# primus.net
KiCad netlist of a schematic drawn in EAGLE
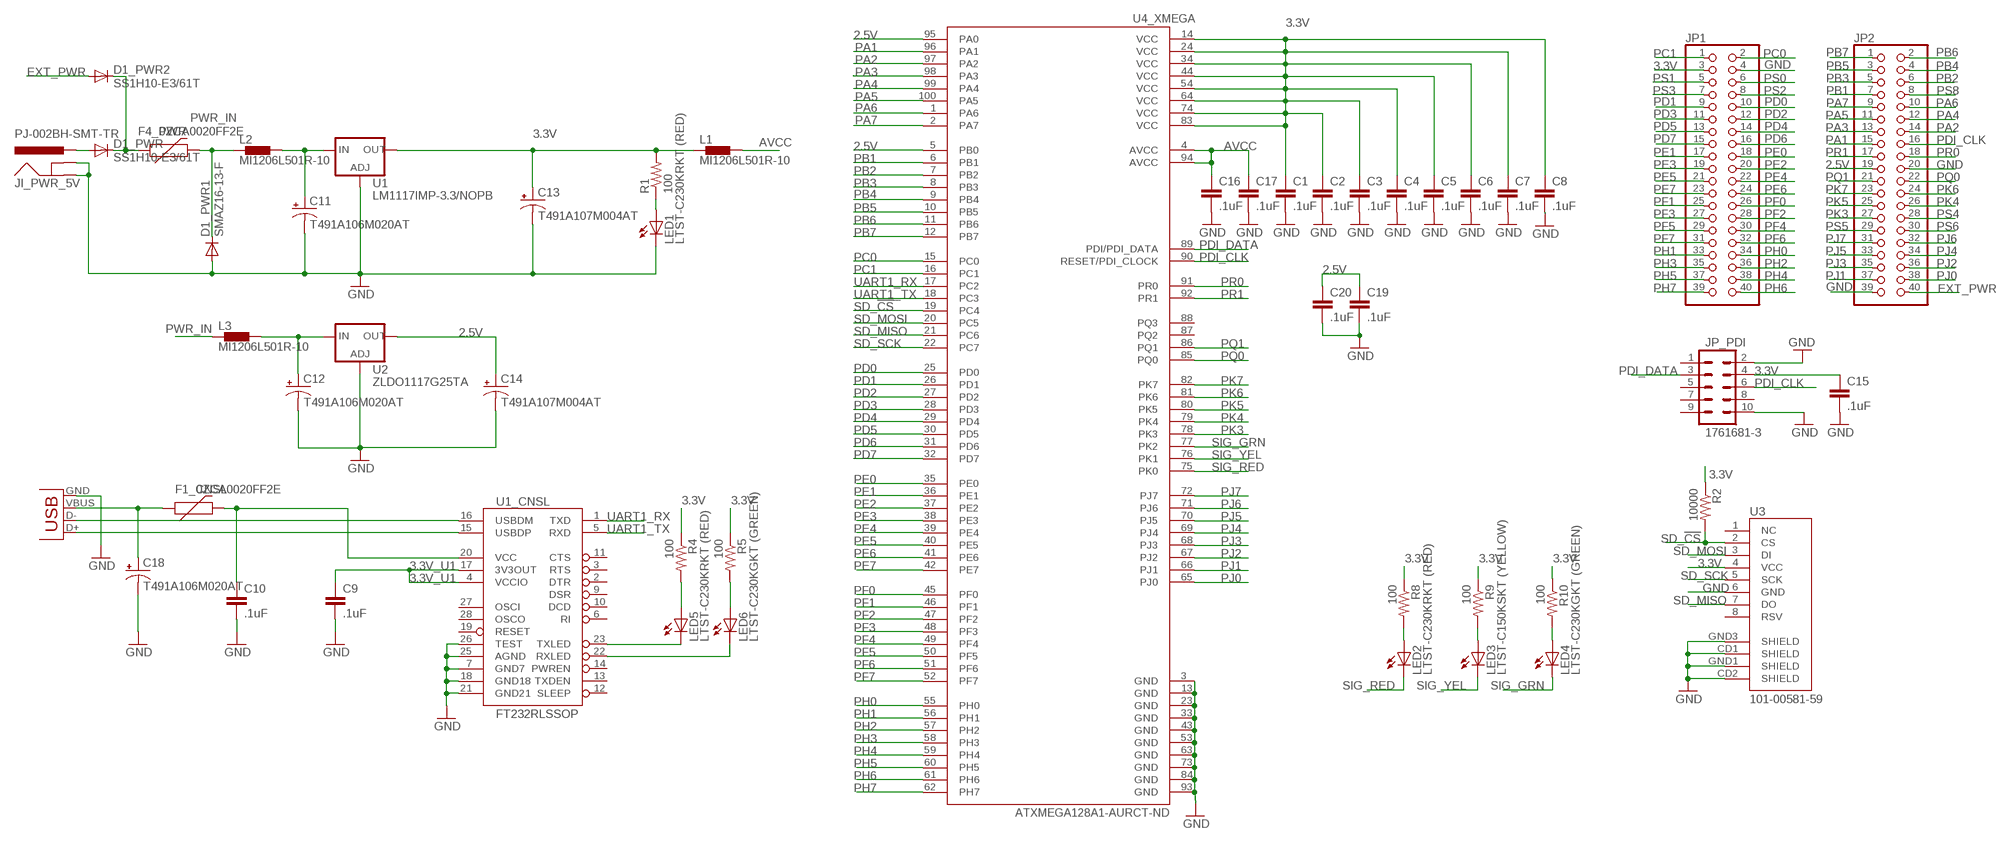
[diagram p0: schematic, sheet 1]

(export (version "E")
  (design (tool "Eeschema 10.0.6"))
  (components
    (comp (ref "C1")
      (value ".1uF")
      (footprint "eagle-import:0603-CAP")
      (libsource (lib "eagle-import") (part "CAP0603-CAP"))
    )
    (comp (ref "C2")
      (value ".1uF")
      (footprint "eagle-import:0603-CAP")
      (libsource (lib "eagle-import") (part "CAP0603-CAP"))
    )
    (comp (ref "C3")
      (value ".1uF")
      (footprint "eagle-import:0603-CAP")
      (libsource (lib "eagle-import") (part "CAP0603-CAP"))
    )
    (comp (ref "C4")
      (value ".1uF")
      (footprint "eagle-import:0603-CAP")
      (libsource (lib "eagle-import") (part "CAP0603-CAP"))
    )
    (comp (ref "C5")
      (value ".1uF")
      (footprint "eagle-import:0603-CAP")
      (libsource (lib "eagle-import") (part "CAP0603-CAP"))
    )
    (comp (ref "C6")
      (value ".1uF")
      (footprint "eagle-import:0603-CAP")
      (libsource (lib "eagle-import") (part "CAP0603-CAP"))
    )
    (comp (ref "C7")
      (value ".1uF")
      (footprint "eagle-import:0603-CAP")
      (libsource (lib "eagle-import") (part "CAP0603-CAP"))
    )
    (comp (ref "C8")
      (value ".1uF")
      (footprint "eagle-import:0603-CAP")
      (libsource (lib "eagle-import") (part "CAP0603-CAP"))
    )
    (comp (ref "C9")
      (value ".1uF")
      (footprint "eagle-import:0603-CAP")
      (libsource (lib "eagle-import") (part "CAP0603-CAP"))
    )
    (comp (ref "C10")
      (value ".1uF")
      (footprint "eagle-import:0603-CAP")
      (libsource (lib "eagle-import") (part "CAP0603-CAP"))
    )
    (comp (ref "C11")
      (value "T491A106M020AT")
      (footprint "eagle-import:EIA3216")
      (libsource (lib "eagle-import") (part "CAP_POL1206"))
    )
    (comp (ref "C12")
      (value "T491A106M020AT")
      (footprint "eagle-import:EIA3216")
      (libsource (lib "eagle-import") (part "CAP_POL1206"))
    )
    (comp (ref "C13")
      (value "T491A107M004AT")
      (footprint "eagle-import:EIA3216")
      (libsource (lib "eagle-import") (part "CAP_POL1206"))
    )
    (comp (ref "C14")
      (value "T491A107M004AT")
      (footprint "eagle-import:EIA3216")
      (libsource (lib "eagle-import") (part "CAP_POL1206"))
    )
    (comp (ref "C15")
      (value ".1uF")
      (footprint "eagle-import:0603-CAP")
      (libsource (lib "eagle-import") (part "CAP0603-CAP"))
    )
    (comp (ref "C16")
      (value ".1uF")
      (footprint "eagle-import:0603-CAP")
      (libsource (lib "eagle-import") (part "CAP0603-CAP"))
    )
    (comp (ref "C17")
      (value ".1uF")
      (footprint "eagle-import:0603-CAP")
      (libsource (lib "eagle-import") (part "CAP0603-CAP"))
    )
    (comp (ref "C18")
      (value "T491A106M020AT")
      (footprint "eagle-import:EIA3216")
      (libsource (lib "eagle-import") (part "CAP_POL1206"))
    )
    (comp (ref "C19")
      (value ".1uF")
      (footprint "eagle-import:0603-CAP")
      (libsource (lib "eagle-import") (part "CAP0603-CAP"))
    )
    (comp (ref "C20")
      (value ".1uF")
      (footprint "eagle-import:0603-CAP")
      (libsource (lib "eagle-import") (part "CAP0603-CAP"))
    )
    (comp (ref "D1_PWR")
      (value "SS1H10-E3/61T")
      (footprint "eagle-import:SMA-DIODE")
      (libsource (lib "eagle-import") (part "DIODESMA"))
    )
    (comp (ref "D1_PWR1")
      (value "SMAZ16-13-F")
      (footprint "eagle-import:SMA-DIODE")
      (libsource (lib "eagle-import") (part "DIODESMA"))
    )
    (comp (ref "D1_PWR2")
      (value "SS1H10-E3/61T")
      (footprint "eagle-import:SMA-DIODE")
      (libsource (lib "eagle-import") (part "DIODESMA"))
    )
    (comp (ref "F1_CNSL")
      (value "0ZCA0020FF2E")
      (footprint "eagle-import:PTC-1206")
      (libsource (lib "eagle-import") (part "PTCSMD"))
    )
    (comp (ref "F4_PWR")
      (value "0ZCA0020FF2E")
      (footprint "eagle-import:PTC-1206")
      (libsource (lib "eagle-import") (part "PTCSMD"))
    )
    (comp (ref "JI_PWR_5V")
      (value "PJ-002BH-SMT-TR")
      (footprint "eagle-import:POWER_JACK_SMD")
      (libsource (lib "eagle-import") (part "POWER_JACKSMD"))
    )
    (comp (ref "JP1")
      (value "PINHD-2X20")
      (footprint "eagle-import:2X20")
      (libsource (lib "eagle-import") (part "PINHD-2X20"))
    )
    (comp (ref "JP2")
      (value "PINHD-2X20")
      (footprint "eagle-import:2X20")
      (libsource (lib "eagle-import") (part "PINHD-2X20"))
    )
    (comp (ref "JP_PDI")
      (value "1761681-3")
      (footprint "eagle-import:2X5-SHROUDED")
      (libsource (lib "eagle-import") (part "M05X2SHD"))
    )
    (comp (ref "L1")
      (value "MI1206L501R-10")
      (footprint "eagle-import:1206")
      (libsource (lib "eagle-import") (part "MI1206L501R-10"))
    )
    (comp (ref "L2")
      (value "MI1206L501R-10")
      (footprint "eagle-import:1206")
      (libsource (lib "eagle-import") (part "MI1206L501R-10"))
    )
    (comp (ref "L3")
      (value "MI1206L501R-10")
      (footprint "eagle-import:1206")
      (libsource (lib "eagle-import") (part "MI1206L501R-10"))
    )
    (comp (ref "LED1")
      (value "LTST-C230KRKT (RED)")
      (footprint "eagle-import:LED-1206")
      (libsource (lib "eagle-import") (part "LED1206"))
    )
    (comp (ref "LED2")
      (value "LTST-C230KRKT (RED)")
      (footprint "eagle-import:LED-1206")
      (libsource (lib "eagle-import") (part "LED1206"))
    )
    (comp (ref "LED3")
      (value "LTST-C150KSKT (YELLOW)")
      (footprint "eagle-import:LED-1206")
      (libsource (lib "eagle-import") (part "LED1206"))
    )
    (comp (ref "LED4")
      (value "LTST-C230KGKT (GREEN)")
      (footprint "eagle-import:LED-1206")
      (libsource (lib "eagle-import") (part "LED1206"))
    )
    (comp (ref "LED5")
      (value "LTST-C230KRKT (RED)")
      (footprint "eagle-import:LED-1206")
      (libsource (lib "eagle-import") (part "LED1206"))
    )
    (comp (ref "LED6")
      (value "LTST-C230KGKT (GREEN)")
      (footprint "eagle-import:LED-1206")
      (libsource (lib "eagle-import") (part "LED1206"))
    )
    (comp (ref "R1")
      (value "100")
      (footprint "eagle-import:0603-RES")
      (libsource (lib "eagle-import") (part "RESISTOR0603-RES"))
    )
    (comp (ref "R2")
      (value "10000")
      (footprint "eagle-import:0603-RES")
      (libsource (lib "eagle-import") (part "RESISTOR0603-RES"))
    )
    (comp (ref "R4")
      (value "100")
      (footprint "eagle-import:0603-RES")
      (libsource (lib "eagle-import") (part "RESISTOR0603-RES"))
    )
    (comp (ref "R5")
      (value "100")
      (footprint "eagle-import:0603-RES")
      (libsource (lib "eagle-import") (part "RESISTOR0603-RES"))
    )
    (comp (ref "R8")
      (value "100")
      (footprint "eagle-import:0603-RES")
      (libsource (lib "eagle-import") (part "RESISTOR0603-RES"))
    )
    (comp (ref "R9")
      (value "100")
      (footprint "eagle-import:0603-RES")
      (libsource (lib "eagle-import") (part "RESISTOR0603-RES"))
    )
    (comp (ref "R10")
      (value "100")
      (footprint "eagle-import:0603-RES")
      (libsource (lib "eagle-import") (part "RESISTOR0603-RES"))
    )
    (comp (ref "U1")
      (value "LM1117IMP-3.3/NOPB")
      (footprint "eagle-import:SOT223")
      (libsource (lib "eagle-import") (part "V_REG_317SMD"))
    )
    (comp (ref "U1_CNSL")
      (value "FT232RLSSOP")
      (footprint "eagle-import:SSOP28DB")
      (libsource (lib "eagle-import") (part "FT232RLSSOP"))
    )
    (comp (ref "U2")
      (value "ZLDO1117G25TA")
      (footprint "eagle-import:SOT223")
      (libsource (lib "eagle-import") (part "V_REG_317SMD"))
    )
    (comp (ref "U3")
      (value "101-00581-59")
      (footprint "eagle-import:MICRO-SD-SOCKET-PP")
      (libsource (lib "eagle-import") (part "USD-SOCKETNEW"))
    )
    (comp (ref "U4_XMEGA")
      (value "ATXMEGA128A1-AURCT-ND")
      (footprint "eagle-import:TQFP-100-14X14MM")
      (libsource (lib "eagle-import") (part "XMEGA-100SMD"))
    )
    (comp (ref "X2_CNSL")
      (value "UX60A-MB-5ST")
      (footprint "eagle-import:USB-MINIB")
      (libsource (lib "eagle-import") (part "USBSMD"))
    )
  )
  (nets
    (net (code "1") (name "/2.5V") (class "Default")
      (node (ref "C14") (pin "A") (pinfunction "+_A") (pintype "passive"))
      (node (ref "C19") (pin "1") (pinfunction "1_1") (pintype "passive"))
      (node (ref "C20") (pin "1") (pinfunction "1_1") (pintype "passive"))
      (node (ref "JP2") (pin "19") (pinfunction "19_19") (pintype "passive"))
      (node (ref "U2") (pin "2") (pinfunction "OUT_2") (pintype "output"))
      (node (ref "U4_XMEGA") (pin "5") (pinfunction "PB0_5") (pintype "bidirectional"))
      (node (ref "U4_XMEGA") (pin "95") (pinfunction "PA0_95") (pintype "bidirectional"))
    )
    (net (code "2") (name "/3.3V") (class "Default")
      (node (ref "C1") (pin "1") (pinfunction "1_1") (pintype "passive"))
      (node (ref "C13") (pin "A") (pinfunction "+_A") (pintype "passive"))
      (node (ref "C15") (pin "1") (pinfunction "1_1") (pintype "passive"))
      (node (ref "C2") (pin "1") (pinfunction "1_1") (pintype "passive"))
      (node (ref "C3") (pin "1") (pinfunction "1_1") (pintype "passive"))
      (node (ref "C4") (pin "1") (pinfunction "1_1") (pintype "passive"))
      (node (ref "C5") (pin "1") (pinfunction "1_1") (pintype "passive"))
      (node (ref "C6") (pin "1") (pinfunction "1_1") (pintype "passive"))
      (node (ref "C7") (pin "1") (pinfunction "1_1") (pintype "passive"))
      (node (ref "C8") (pin "1") (pinfunction "1_1") (pintype "passive"))
      (node (ref "JP1") (pin "3") (pinfunction "3_3") (pintype "passive"))
      (node (ref "JP_PDI") (pin "4") (pinfunction "4_4") (pintype "passive"))
      (node (ref "L1") (pin "1") (pinfunction "1_1") (pintype "passive"))
      (node (ref "R1") (pin "2") (pinfunction "2_2") (pintype "passive"))
      (node (ref "R10") (pin "1") (pinfunction "1_1") (pintype "passive"))
      (node (ref "R2") (pin "1") (pinfunction "1_1") (pintype "passive"))
      (node (ref "R4") (pin "1") (pinfunction "1_1") (pintype "passive"))
      (node (ref "R5") (pin "1") (pinfunction "1_1") (pintype "passive"))
      (node (ref "R8") (pin "1") (pinfunction "1_1") (pintype "passive"))
      (node (ref "R9") (pin "1") (pinfunction "1_1") (pintype "passive"))
      (node (ref "U1") (pin "2") (pinfunction "OUT_2") (pintype "output"))
      (node (ref "U3") (pin "4") (pinfunction "VCC_4") (pintype "bidirectional"))
      (node (ref "U4_XMEGA") (pin "14") (pinfunction "VCC_14") (pintype "bidirectional"))
      (node (ref "U4_XMEGA") (pin "24") (pinfunction "VCC_24") (pintype "bidirectional"))
      (node (ref "U4_XMEGA") (pin "34") (pinfunction "VCC_34") (pintype "bidirectional"))
      (node (ref "U4_XMEGA") (pin "44") (pinfunction "VCC_44") (pintype "bidirectional"))
      (node (ref "U4_XMEGA") (pin "54") (pinfunction "VCC_54") (pintype "bidirectional"))
      (node (ref "U4_XMEGA") (pin "64") (pinfunction "VCC_64") (pintype "bidirectional"))
      (node (ref "U4_XMEGA") (pin "74") (pinfunction "VCC_74") (pintype "bidirectional"))
      (node (ref "U4_XMEGA") (pin "83") (pinfunction "VCC_83") (pintype "bidirectional"))
    )
    (net (code "3") (name "/3.3V_U1") (class "Default")
      (node (ref "C9") (pin "1") (pinfunction "1_1") (pintype "passive"))
      (node (ref "U1_CNSL") (pin "17") (pinfunction "3V3OUT_17") (pintype "output"))
      (node (ref "U1_CNSL") (pin "4") (pinfunction "VCCIO_4") (pintype "power_in"))
    )
    (net (code "4") (name "/AVCC") (class "Default")
      (node (ref "C16") (pin "1") (pinfunction "1_1") (pintype "passive"))
      (node (ref "C17") (pin "1") (pinfunction "1_1") (pintype "passive"))
      (node (ref "L1") (pin "2") (pinfunction "2_2") (pintype "passive"))
      (node (ref "U4_XMEGA") (pin "4") (pinfunction "AVCC_4") (pintype "bidirectional"))
      (node (ref "U4_XMEGA") (pin "94") (pinfunction "AVCC_94") (pintype "bidirectional"))
    )
    (net (code "5") (name "/EXT_PWR") (class "Default")
      (node (ref "D1_PWR2") (pin "A") (pinfunction "A_A") (pintype "passive"))
      (node (ref "JP2") (pin "40") (pinfunction "40_40") (pintype "passive"))
    )
    (net (code "6") (name "/PA1") (class "Default")
      (node (ref "JP2") (pin "15") (pinfunction "15_15") (pintype "passive"))
      (node (ref "U4_XMEGA") (pin "96") (pinfunction "PA1_96") (pintype "bidirectional"))
    )
    (net (code "7") (name "/PA2") (class "Default")
      (node (ref "JP2") (pin "14") (pinfunction "14_14") (pintype "passive"))
      (node (ref "U4_XMEGA") (pin "97") (pinfunction "PA2_97") (pintype "bidirectional"))
    )
    (net (code "8") (name "/PA3") (class "Default")
      (node (ref "JP2") (pin "13") (pinfunction "13_13") (pintype "passive"))
      (node (ref "U4_XMEGA") (pin "98") (pinfunction "PA3_98") (pintype "bidirectional"))
    )
    (net (code "9") (name "/PA4") (class "Default")
      (node (ref "JP2") (pin "12") (pinfunction "12_12") (pintype "passive"))
      (node (ref "U4_XMEGA") (pin "99") (pinfunction "PA4_99") (pintype "bidirectional"))
    )
    (net (code "10") (name "/PA5") (class "Default")
      (node (ref "JP2") (pin "11") (pinfunction "11_11") (pintype "passive"))
      (node (ref "U4_XMEGA") (pin "100") (pinfunction "PA5_100") (pintype "bidirectional"))
    )
    (net (code "11") (name "/PA6") (class "Default")
      (node (ref "JP2") (pin "10") (pinfunction "10_10") (pintype "passive"))
      (node (ref "U4_XMEGA") (pin "1") (pinfunction "PA6_1") (pintype "bidirectional"))
    )
    (net (code "12") (name "/PA7") (class "Default")
      (node (ref "JP2") (pin "9") (pinfunction "9_9") (pintype "passive"))
      (node (ref "U4_XMEGA") (pin "2") (pinfunction "PA7_2") (pintype "bidirectional"))
    )
    (net (code "13") (name "/PB1") (class "Default")
      (node (ref "JP2") (pin "7") (pinfunction "7_7") (pintype "passive"))
      (node (ref "U4_XMEGA") (pin "6") (pinfunction "PB1_6") (pintype "bidirectional"))
    )
    (net (code "14") (name "/PB2") (class "Default")
      (node (ref "JP2") (pin "6") (pinfunction "6_6") (pintype "passive"))
      (node (ref "U4_XMEGA") (pin "7") (pinfunction "PB2_7") (pintype "bidirectional"))
    )
    (net (code "15") (name "/PB3") (class "Default")
      (node (ref "JP2") (pin "5") (pinfunction "5_5") (pintype "passive"))
      (node (ref "U4_XMEGA") (pin "8") (pinfunction "PB3_8") (pintype "bidirectional"))
    )
    (net (code "16") (name "/PB4") (class "Default")
      (node (ref "JP2") (pin "4") (pinfunction "4_4") (pintype "passive"))
      (node (ref "U4_XMEGA") (pin "9") (pinfunction "PB4_9") (pintype "bidirectional"))
    )
    (net (code "17") (name "/PB5") (class "Default")
      (node (ref "JP2") (pin "3") (pinfunction "3_3") (pintype "passive"))
      (node (ref "U4_XMEGA") (pin "10") (pinfunction "PB5_10") (pintype "bidirectional"))
    )
    (net (code "18") (name "/PB6") (class "Default")
      (node (ref "JP2") (pin "2") (pinfunction "2_2") (pintype "passive"))
      (node (ref "U4_XMEGA") (pin "11") (pinfunction "PB6_11") (pintype "bidirectional"))
    )
    (net (code "19") (name "/PB7") (class "Default")
      (node (ref "JP2") (pin "1") (pinfunction "1_1") (pintype "passive"))
      (node (ref "U4_XMEGA") (pin "12") (pinfunction "PB7_12") (pintype "bidirectional"))
    )
    (net (code "20") (name "/PC0") (class "Default")
      (node (ref "JP1") (pin "2") (pinfunction "2_2") (pintype "passive"))
      (node (ref "U4_XMEGA") (pin "15") (pinfunction "PC0_15") (pintype "bidirectional"))
    )
    (net (code "21") (name "/PC1") (class "Default")
      (node (ref "JP1") (pin "1") (pinfunction "1_1") (pintype "passive"))
      (node (ref "U4_XMEGA") (pin "16") (pinfunction "PC1_16") (pintype "bidirectional"))
    )
    (net (code "22") (name "/PD0") (class "Default")
      (node (ref "JP1") (pin "10") (pinfunction "10_10") (pintype "passive"))
      (node (ref "U4_XMEGA") (pin "25") (pinfunction "PD0_25") (pintype "bidirectional"))
    )
    (net (code "23") (name "/PD1") (class "Default")
      (node (ref "JP1") (pin "9") (pinfunction "9_9") (pintype "passive"))
      (node (ref "U4_XMEGA") (pin "26") (pinfunction "PD1_26") (pintype "bidirectional"))
    )
    (net (code "24") (name "/PD2") (class "Default")
      (node (ref "JP1") (pin "12") (pinfunction "12_12") (pintype "passive"))
      (node (ref "U4_XMEGA") (pin "27") (pinfunction "PD2_27") (pintype "bidirectional"))
    )
    (net (code "25") (name "/PD3") (class "Default")
      (node (ref "JP1") (pin "11") (pinfunction "11_11") (pintype "passive"))
      (node (ref "U4_XMEGA") (pin "28") (pinfunction "PD3_28") (pintype "bidirectional"))
    )
    (net (code "26") (name "/PD4") (class "Default")
      (node (ref "JP1") (pin "14") (pinfunction "14_14") (pintype "passive"))
      (node (ref "U4_XMEGA") (pin "29") (pinfunction "PD4_29") (pintype "bidirectional"))
    )
    (net (code "27") (name "/PD5") (class "Default")
      (node (ref "JP1") (pin "13") (pinfunction "13_13") (pintype "passive"))
      (node (ref "U4_XMEGA") (pin "30") (pinfunction "PD5_30") (pintype "bidirectional"))
    )
    (net (code "28") (name "/PD6") (class "Default")
      (node (ref "JP1") (pin "16") (pinfunction "16_16") (pintype "passive"))
      (node (ref "U4_XMEGA") (pin "31") (pinfunction "PD6_31") (pintype "bidirectional"))
    )
    (net (code "29") (name "/PD7") (class "Default")
      (node (ref "JP1") (pin "15") (pinfunction "15_15") (pintype "passive"))
      (node (ref "U4_XMEGA") (pin "32") (pinfunction "PD7_32") (pintype "bidirectional"))
    )
    (net (code "30") (name "/PDI_CLK") (class "Default")
      (node (ref "JP2") (pin "16") (pinfunction "16_16") (pintype "passive"))
      (node (ref "JP_PDI") (pin "6") (pinfunction "6_6") (pintype "passive"))
      (node (ref "U4_XMEGA") (pin "90") (pinfunction "RESET/PDI_CLOCK_90") (pintype "bidirectional"))
    )
    (net (code "31") (name "/PDI_DATA") (class "Default")
      (node (ref "JP_PDI") (pin "3") (pinfunction "3_3") (pintype "passive"))
      (node (ref "U4_XMEGA") (pin "89") (pinfunction "PDI/PDI_DATA_89") (pintype "bidirectional"))
    )
    (net (code "32") (name "/PE0") (class "Default")
      (node (ref "JP1") (pin "18") (pinfunction "18_18") (pintype "passive"))
      (node (ref "U4_XMEGA") (pin "35") (pinfunction "PE0_35") (pintype "bidirectional"))
    )
    (net (code "33") (name "/PE1") (class "Default")
      (node (ref "JP1") (pin "17") (pinfunction "17_17") (pintype "passive"))
      (node (ref "U4_XMEGA") (pin "36") (pinfunction "PE1_36") (pintype "bidirectional"))
    )
    (net (code "34") (name "/PE2") (class "Default")
      (node (ref "JP1") (pin "20") (pinfunction "20_20") (pintype "passive"))
      (node (ref "U4_XMEGA") (pin "37") (pinfunction "PE2_37") (pintype "bidirectional"))
    )
    (net (code "35") (name "/PE3") (class "Default")
      (node (ref "JP1") (pin "19") (pinfunction "19_19") (pintype "passive"))
      (node (ref "U4_XMEGA") (pin "38") (pinfunction "PE3_38") (pintype "bidirectional"))
    )
    (net (code "36") (name "/PE4") (class "Default")
      (node (ref "JP1") (pin "22") (pinfunction "22_22") (pintype "passive"))
      (node (ref "U4_XMEGA") (pin "39") (pinfunction "PE4_39") (pintype "bidirectional"))
    )
    (net (code "37") (name "/PE5") (class "Default")
      (node (ref "JP1") (pin "21") (pinfunction "21_21") (pintype "passive"))
      (node (ref "U4_XMEGA") (pin "40") (pinfunction "PE5_40") (pintype "bidirectional"))
    )
    (net (code "38") (name "/PE6") (class "Default")
      (node (ref "JP1") (pin "24") (pinfunction "24_24") (pintype "passive"))
      (node (ref "U4_XMEGA") (pin "41") (pinfunction "PE6_41") (pintype "bidirectional"))
    )
    (net (code "39") (name "/PE7") (class "Default")
      (node (ref "JP1") (pin "23") (pinfunction "23_23") (pintype "passive"))
      (node (ref "U4_XMEGA") (pin "42") (pinfunction "PE7_42") (pintype "bidirectional"))
    )
    (net (code "40") (name "/PF0") (class "Default")
      (node (ref "JP1") (pin "26") (pinfunction "26_26") (pintype "passive"))
      (node (ref "U4_XMEGA") (pin "45") (pinfunction "PF0_45") (pintype "bidirectional"))
    )
    (net (code "41") (name "/PF1") (class "Default")
      (node (ref "JP1") (pin "25") (pinfunction "25_25") (pintype "passive"))
      (node (ref "U4_XMEGA") (pin "46") (pinfunction "PF1_46") (pintype "bidirectional"))
    )
    (net (code "42") (name "/PF2") (class "Default")
      (node (ref "JP1") (pin "28") (pinfunction "28_28") (pintype "passive"))
      (node (ref "U4_XMEGA") (pin "47") (pinfunction "PF2_47") (pintype "bidirectional"))
    )
    (net (code "43") (name "/PF3") (class "Default")
      (node (ref "JP1") (pin "27") (pinfunction "27_27") (pintype "passive"))
      (node (ref "U4_XMEGA") (pin "48") (pinfunction "PF3_48") (pintype "bidirectional"))
    )
    (net (code "44") (name "/PF4") (class "Default")
      (node (ref "JP1") (pin "30") (pinfunction "30_30") (pintype "passive"))
      (node (ref "U4_XMEGA") (pin "49") (pinfunction "PF4_49") (pintype "bidirectional"))
    )
    (net (code "45") (name "/PF5") (class "Default")
      (node (ref "JP1") (pin "29") (pinfunction "29_29") (pintype "passive"))
      (node (ref "U4_XMEGA") (pin "50") (pinfunction "PF5_50") (pintype "bidirectional"))
    )
    (net (code "46") (name "/PF6") (class "Default")
      (node (ref "JP1") (pin "32") (pinfunction "32_32") (pintype "passive"))
      (node (ref "U4_XMEGA") (pin "51") (pinfunction "PF6_51") (pintype "bidirectional"))
    )
    (net (code "47") (name "/PF7") (class "Default")
      (node (ref "JP1") (pin "31") (pinfunction "31_31") (pintype "passive"))
      (node (ref "U4_XMEGA") (pin "52") (pinfunction "PF7_52") (pintype "bidirectional"))
    )
    (net (code "48") (name "/PH0") (class "Default")
      (node (ref "JP1") (pin "34") (pinfunction "34_34") (pintype "passive"))
      (node (ref "U4_XMEGA") (pin "55") (pinfunction "PH0_55") (pintype "bidirectional"))
    )
    (net (code "49") (name "/PH1") (class "Default")
      (node (ref "JP1") (pin "33") (pinfunction "33_33") (pintype "passive"))
      (node (ref "U4_XMEGA") (pin "56") (pinfunction "PH1_56") (pintype "bidirectional"))
    )
    (net (code "50") (name "/PH2") (class "Default")
      (node (ref "JP1") (pin "36") (pinfunction "36_36") (pintype "passive"))
      (node (ref "U4_XMEGA") (pin "57") (pinfunction "PH2_57") (pintype "bidirectional"))
    )
    (net (code "51") (name "/PH3") (class "Default")
      (node (ref "JP1") (pin "35") (pinfunction "35_35") (pintype "passive"))
      (node (ref "U4_XMEGA") (pin "58") (pinfunction "PH3_58") (pintype "bidirectional"))
    )
    (net (code "52") (name "/PH4") (class "Default")
      (node (ref "JP1") (pin "38") (pinfunction "38_38") (pintype "passive"))
      (node (ref "U4_XMEGA") (pin "59") (pinfunction "PH4_59") (pintype "bidirectional"))
    )
    (net (code "53") (name "/PH5") (class "Default")
      (node (ref "JP1") (pin "37") (pinfunction "37_37") (pintype "passive"))
      (node (ref "U4_XMEGA") (pin "60") (pinfunction "PH5_60") (pintype "bidirectional"))
    )
    (net (code "54") (name "/PH6") (class "Default")
      (node (ref "JP1") (pin "40") (pinfunction "40_40") (pintype "passive"))
      (node (ref "U4_XMEGA") (pin "61") (pinfunction "PH6_61") (pintype "bidirectional"))
    )
    (net (code "55") (name "/PH7") (class "Default")
      (node (ref "JP1") (pin "39") (pinfunction "39_39") (pintype "passive"))
      (node (ref "U4_XMEGA") (pin "62") (pinfunction "PH7_62") (pintype "bidirectional"))
    )
    (net (code "56") (name "/PJ0") (class "Default")
      (node (ref "JP2") (pin "38") (pinfunction "38_38") (pintype "passive"))
      (node (ref "U4_XMEGA") (pin "65") (pinfunction "PJ0_65") (pintype "bidirectional"))
    )
    (net (code "57") (name "/PJ1") (class "Default")
      (node (ref "JP2") (pin "37") (pinfunction "37_37") (pintype "passive"))
      (node (ref "U4_XMEGA") (pin "66") (pinfunction "PJ1_66") (pintype "bidirectional"))
    )
    (net (code "58") (name "/PJ2") (class "Default")
      (node (ref "JP2") (pin "36") (pinfunction "36_36") (pintype "passive"))
      (node (ref "U4_XMEGA") (pin "67") (pinfunction "PJ2_67") (pintype "bidirectional"))
    )
    (net (code "59") (name "/PJ3") (class "Default")
      (node (ref "JP2") (pin "35") (pinfunction "35_35") (pintype "passive"))
      (node (ref "U4_XMEGA") (pin "68") (pinfunction "PJ3_68") (pintype "bidirectional"))
    )
    (net (code "60") (name "/PJ4") (class "Default")
      (node (ref "JP2") (pin "34") (pinfunction "34_34") (pintype "passive"))
      (node (ref "U4_XMEGA") (pin "69") (pinfunction "PJ4_69") (pintype "bidirectional"))
    )
    (net (code "61") (name "/PJ5") (class "Default")
      (node (ref "JP2") (pin "33") (pinfunction "33_33") (pintype "passive"))
      (node (ref "U4_XMEGA") (pin "70") (pinfunction "PJ5_70") (pintype "bidirectional"))
    )
    (net (code "62") (name "/PJ6") (class "Default")
      (node (ref "JP2") (pin "32") (pinfunction "32_32") (pintype "passive"))
      (node (ref "U4_XMEGA") (pin "71") (pinfunction "PJ6_71") (pintype "bidirectional"))
    )
    (net (code "63") (name "/PJ7") (class "Default")
      (node (ref "JP2") (pin "31") (pinfunction "31_31") (pintype "passive"))
      (node (ref "U4_XMEGA") (pin "72") (pinfunction "PJ7_72") (pintype "bidirectional"))
    )
    (net (code "64") (name "/PK3") (class "Default")
      (node (ref "JP2") (pin "27") (pinfunction "27_27") (pintype "passive"))
      (node (ref "U4_XMEGA") (pin "78") (pinfunction "PK3_78") (pintype "bidirectional"))
    )
    (net (code "65") (name "/PK4") (class "Default")
      (node (ref "JP2") (pin "26") (pinfunction "26_26") (pintype "passive"))
      (node (ref "U4_XMEGA") (pin "79") (pinfunction "PK4_79") (pintype "bidirectional"))
    )
    (net (code "66") (name "/PK5") (class "Default")
      (node (ref "JP2") (pin "25") (pinfunction "25_25") (pintype "passive"))
      (node (ref "U4_XMEGA") (pin "80") (pinfunction "PK5_80") (pintype "bidirectional"))
    )
    (net (code "67") (name "/PK6") (class "Default")
      (node (ref "JP2") (pin "24") (pinfunction "24_24") (pintype "passive"))
      (node (ref "U4_XMEGA") (pin "81") (pinfunction "PK6_81") (pintype "bidirectional"))
    )
    (net (code "68") (name "/PK7") (class "Default")
      (node (ref "JP2") (pin "23") (pinfunction "23_23") (pintype "passive"))
      (node (ref "U4_XMEGA") (pin "82") (pinfunction "PK7_82") (pintype "bidirectional"))
    )
    (net (code "69") (name "/PQ0") (class "Default")
      (node (ref "JP2") (pin "22") (pinfunction "22_22") (pintype "passive"))
      (node (ref "U4_XMEGA") (pin "85") (pinfunction "PQ0_85") (pintype "bidirectional"))
    )
    (net (code "70") (name "/PQ1") (class "Default")
      (node (ref "JP2") (pin "21") (pinfunction "21_21") (pintype "passive"))
      (node (ref "U4_XMEGA") (pin "86") (pinfunction "PQ1_86") (pintype "bidirectional"))
    )
    (net (code "71") (name "/PR0") (class "Default")
      (node (ref "JP2") (pin "18") (pinfunction "18_18") (pintype "passive"))
      (node (ref "U4_XMEGA") (pin "91") (pinfunction "PR0_91") (pintype "bidirectional"))
    )
    (net (code "72") (name "/PR1") (class "Default")
      (node (ref "JP2") (pin "17") (pinfunction "17_17") (pintype "passive"))
      (node (ref "U4_XMEGA") (pin "92") (pinfunction "PR1_92") (pintype "bidirectional"))
    )
    (net (code "73") (name "/PS0") (class "Default")
      (node (ref "JP1") (pin "6") (pinfunction "6_6") (pintype "passive"))
    )
    (net (code "74") (name "/PS1") (class "Default")
      (node (ref "JP1") (pin "5") (pinfunction "5_5") (pintype "passive"))
    )
    (net (code "75") (name "/PS2") (class "Default")
      (node (ref "JP1") (pin "8") (pinfunction "8_8") (pintype "passive"))
    )
    (net (code "76") (name "/PS3") (class "Default")
      (node (ref "JP1") (pin "7") (pinfunction "7_7") (pintype "passive"))
    )
    (net (code "77") (name "/PS4") (class "Default")
      (node (ref "JP2") (pin "28") (pinfunction "28_28") (pintype "passive"))
    )
    (net (code "78") (name "/PS5") (class "Default")
      (node (ref "JP2") (pin "29") (pinfunction "29_29") (pintype "passive"))
    )
    (net (code "79") (name "/PS6") (class "Default")
      (node (ref "JP2") (pin "30") (pinfunction "30_30") (pintype "passive"))
    )
    (net (code "80") (name "/PS8") (class "Default")
      (node (ref "JP2") (pin "8") (pinfunction "8_8") (pintype "passive"))
    )
    (net (code "81") (name "/PWR_IN") (class "Default")
      (node (ref "D1_PWR1") (pin "C") (pinfunction "C_C") (pintype "passive"))
      (node (ref "F4_PWR") (pin "2") (pinfunction "2_2") (pintype "bidirectional"))
      (node (ref "L2") (pin "1") (pinfunction "1_1") (pintype "passive"))
      (node (ref "L3") (pin "1") (pinfunction "1_1") (pintype "passive"))
    )
    (net (code "82") (name "/SD_MISO") (class "Default")
      (node (ref "U3") (pin "7") (pinfunction "DO_7") (pintype "bidirectional"))
      (node (ref "U4_XMEGA") (pin "21") (pinfunction "PC6_21") (pintype "bidirectional"))
    )
    (net (code "83") (name "/SD_MOSI") (class "Default")
      (node (ref "U3") (pin "3") (pinfunction "DI_3") (pintype "bidirectional"))
      (node (ref "U4_XMEGA") (pin "20") (pinfunction "PC5_20") (pintype "bidirectional"))
    )
    (net (code "84") (name "/SD_SCK") (class "Default")
      (node (ref "U3") (pin "5") (pinfunction "SCK_5") (pintype "bidirectional"))
      (node (ref "U4_XMEGA") (pin "22") (pinfunction "PC7_22") (pintype "bidirectional"))
    )
    (net (code "85") (name "/SD_~{CS}") (class "Default")
      (node (ref "R2") (pin "2") (pinfunction "2_2") (pintype "passive"))
      (node (ref "U3") (pin "2") (pinfunction "CS_2") (pintype "bidirectional"))
      (node (ref "U4_XMEGA") (pin "19") (pinfunction "PC4_19") (pintype "bidirectional"))
    )
    (net (code "86") (name "/SIG_GRN") (class "Default")
      (node (ref "LED4") (pin "C") (pinfunction "C_C") (pintype "passive"))
      (node (ref "U4_XMEGA") (pin "77") (pinfunction "PK2_77") (pintype "bidirectional"))
    )
    (net (code "87") (name "/SIG_RED") (class "Default")
      (node (ref "LED2") (pin "C") (pinfunction "C_C") (pintype "passive"))
      (node (ref "U4_XMEGA") (pin "75") (pinfunction "PK0_75") (pintype "bidirectional"))
    )
    (net (code "88") (name "/SIG_YEL") (class "Default")
      (node (ref "LED3") (pin "C") (pinfunction "C_C") (pintype "passive"))
      (node (ref "U4_XMEGA") (pin "76") (pinfunction "PK1_76") (pintype "bidirectional"))
    )
    (net (code "89") (name "/UART1_RX") (class "Default")
      (node (ref "U1_CNSL") (pin "1") (pinfunction "TXD_1") (pintype "output"))
      (node (ref "U4_XMEGA") (pin "17") (pinfunction "PC2_17") (pintype "bidirectional"))
    )
    (net (code "90") (name "/UART1_TX") (class "Default")
      (node (ref "U1_CNSL") (pin "5") (pinfunction "RXD_5") (pintype "input"))
      (node (ref "U4_XMEGA") (pin "18") (pinfunction "PC3_18") (pintype "bidirectional"))
    )
    (net (code "91") (name "GND") (class "Default")
      (node (ref "C1") (pin "2") (pinfunction "2_2") (pintype "passive"))
      (node (ref "C10") (pin "2") (pinfunction "2_2") (pintype "passive"))
      (node (ref "C11") (pin "C") (pinfunction "-_C") (pintype "passive"))
      (node (ref "C12") (pin "C") (pinfunction "-_C") (pintype "passive"))
      (node (ref "C13") (pin "C") (pinfunction "-_C") (pintype "passive"))
      (node (ref "C14") (pin "C") (pinfunction "-_C") (pintype "passive"))
      (node (ref "C15") (pin "2") (pinfunction "2_2") (pintype "passive"))
      (node (ref "C16") (pin "2") (pinfunction "2_2") (pintype "passive"))
      (node (ref "C17") (pin "2") (pinfunction "2_2") (pintype "passive"))
      (node (ref "C18") (pin "C") (pinfunction "-_C") (pintype "passive"))
      (node (ref "C19") (pin "2") (pinfunction "2_2") (pintype "passive"))
      (node (ref "C2") (pin "2") (pinfunction "2_2") (pintype "passive"))
      (node (ref "C20") (pin "2") (pinfunction "2_2") (pintype "passive"))
      (node (ref "C3") (pin "2") (pinfunction "2_2") (pintype "passive"))
      (node (ref "C4") (pin "2") (pinfunction "2_2") (pintype "passive"))
      (node (ref "C5") (pin "2") (pinfunction "2_2") (pintype "passive"))
      (node (ref "C6") (pin "2") (pinfunction "2_2") (pintype "passive"))
      (node (ref "C7") (pin "2") (pinfunction "2_2") (pintype "passive"))
      (node (ref "C8") (pin "2") (pinfunction "2_2") (pintype "passive"))
      (node (ref "C9") (pin "2") (pinfunction "2_2") (pintype "passive"))
      (node (ref "D1_PWR1") (pin "A") (pinfunction "A_A") (pintype "passive"))
      (node (ref "JI_PWR_5V") (pin "GND") (pinfunction "GNDBREAK_GND") (pintype "bidirectional"))
      (node (ref "JI_PWR_5V") (pin "P$4") (pinfunction "GND_P$4") (pintype "bidirectional"))
      (node (ref "JP1") (pin "4") (pinfunction "4_4") (pintype "passive"))
      (node (ref "JP2") (pin "20") (pinfunction "20_20") (pintype "passive"))
      (node (ref "JP2") (pin "39") (pinfunction "39_39") (pintype "passive"))
      (node (ref "JP_PDI") (pin "10") (pinfunction "10_10") (pintype "passive"))
      (node (ref "JP_PDI") (pin "2") (pinfunction "2_2") (pintype "passive"))
      (node (ref "LED1") (pin "C") (pinfunction "C_C") (pintype "passive"))
      (node (ref "U1") (pin "1") (pinfunction "ADJ_1") (pintype "input"))
      (node (ref "U1_CNSL") (pin "18") (pinfunction "GND18_18") (pintype "power_in"))
      (node (ref "U1_CNSL") (pin "21") (pinfunction "GND21_21") (pintype "power_in"))
      (node (ref "U1_CNSL") (pin "25") (pinfunction "AGND_25") (pintype "power_in"))
      (node (ref "U1_CNSL") (pin "26") (pinfunction "TEST_26") (pintype "input"))
      (node (ref "U1_CNSL") (pin "7") (pinfunction "GND7_7") (pintype "power_in"))
      (node (ref "U2") (pin "1") (pinfunction "ADJ_1") (pintype "input"))
      (node (ref "U3") (pin "6") (pinfunction "GND_6") (pintype "bidirectional"))
      (node (ref "U3") (pin "CD1") (pinfunction "SHIELD_CD1") (pintype "bidirectional"))
      (node (ref "U3") (pin "CD2") (pinfunction "SHIELD_CD2") (pintype "bidirectional"))
      (node (ref "U3") (pin "GND1") (pinfunction "SHIELD_GND1") (pintype "bidirectional"))
      (node (ref "U3") (pin "GND3") (pinfunction "SHIELD_GND3") (pintype "bidirectional"))
      (node (ref "U4_XMEGA") (pin "13") (pinfunction "GND_13") (pintype "bidirectional"))
      (node (ref "U4_XMEGA") (pin "23") (pinfunction "GND_23") (pintype "bidirectional"))
      (node (ref "U4_XMEGA") (pin "3") (pinfunction "GND_3") (pintype "bidirectional"))
      (node (ref "U4_XMEGA") (pin "33") (pinfunction "GND_33") (pintype "bidirectional"))
      (node (ref "U4_XMEGA") (pin "43") (pinfunction "GND_43") (pintype "bidirectional"))
      (node (ref "U4_XMEGA") (pin "53") (pinfunction "GND_53") (pintype "bidirectional"))
      (node (ref "U4_XMEGA") (pin "63") (pinfunction "GND_63") (pintype "bidirectional"))
      (node (ref "U4_XMEGA") (pin "73") (pinfunction "GND_73") (pintype "bidirectional"))
      (node (ref "U4_XMEGA") (pin "84") (pinfunction "GND_84") (pintype "bidirectional"))
      (node (ref "U4_XMEGA") (pin "93") (pinfunction "GND_93") (pintype "bidirectional"))
      (node (ref "X2_CNSL") (pin "GND") (pinfunction "GND_GND") (pintype "bidirectional"))
    )
    (net (code "92") (name "Net-(C11-+)") (class "Default")
      (node (ref "C11") (pin "A") (pinfunction "+_A") (pintype "passive"))
      (node (ref "L2") (pin "2") (pinfunction "2_2") (pintype "passive"))
      (node (ref "U1") (pin "3") (pinfunction "IN_3") (pintype "input"))
    )
    (net (code "93") (name "Net-(C12-+)") (class "Default")
      (node (ref "C12") (pin "A") (pinfunction "+_A") (pintype "passive"))
      (node (ref "L3") (pin "2") (pinfunction "2_2") (pintype "passive"))
      (node (ref "U2") (pin "3") (pinfunction "IN_3") (pintype "input"))
    )
    (net (code "94") (name "Net-(C18-+)") (class "Default")
      (node (ref "C18") (pin "A") (pinfunction "+_A") (pintype "passive"))
      (node (ref "F1_CNSL") (pin "1") (pinfunction "1_1") (pintype "bidirectional"))
      (node (ref "X2_CNSL") (pin "VBUS") (pinfunction "VBUS_VBUS") (pintype "bidirectional"))
    )
    (net (code "95") (name "Net-(D1_PWR-PadC)") (class "Default")
      (node (ref "D1_PWR") (pin "C") (pinfunction "C_C") (pintype "passive"))
      (node (ref "D1_PWR2") (pin "C") (pinfunction "C_C") (pintype "passive"))
      (node (ref "F4_PWR") (pin "1") (pinfunction "1_1") (pintype "bidirectional"))
    )
    (net (code "96") (name "Net-(JI_PWR_5V-PWR)") (class "Default")
      (node (ref "D1_PWR") (pin "A") (pinfunction "A_A") (pintype "passive"))
      (node (ref "JI_PWR_5V") (pin "VIN0") (pinfunction "PWR_VIN0") (pintype "bidirectional"))
    )
    (net (code "97") (name "Net-(LED1-PadA)") (class "Default")
      (node (ref "LED1") (pin "A") (pinfunction "A_A") (pintype "passive"))
      (node (ref "R1") (pin "1") (pinfunction "1_1") (pintype "passive"))
    )
    (net (code "98") (name "Net-(LED2-PadA)") (class "Default")
      (node (ref "LED2") (pin "A") (pinfunction "A_A") (pintype "passive"))
      (node (ref "R8") (pin "2") (pinfunction "2_2") (pintype "passive"))
    )
    (net (code "99") (name "Net-(LED3-PadA)") (class "Default")
      (node (ref "LED3") (pin "A") (pinfunction "A_A") (pintype "passive"))
      (node (ref "R9") (pin "2") (pinfunction "2_2") (pintype "passive"))
    )
    (net (code "100") (name "Net-(LED4-PadA)") (class "Default")
      (node (ref "LED4") (pin "A") (pinfunction "A_A") (pintype "passive"))
      (node (ref "R10") (pin "2") (pinfunction "2_2") (pintype "passive"))
    )
    (net (code "101") (name "Net-(LED5-PadA)") (class "Default")
      (node (ref "LED5") (pin "A") (pinfunction "A_A") (pintype "passive"))
      (node (ref "R4") (pin "2") (pinfunction "2_2") (pintype "passive"))
    )
    (net (code "102") (name "Net-(LED6-PadA)") (class "Default")
      (node (ref "LED6") (pin "A") (pinfunction "A_A") (pintype "passive"))
      (node (ref "R5") (pin "2") (pinfunction "2_2") (pintype "passive"))
    )
    (net (code "103") (name "Net-(U1_CNSL-RXLED)") (class "Default")
      (node (ref "LED6") (pin "C") (pinfunction "C_C") (pintype "passive"))
      (node (ref "U1_CNSL") (pin "22") (pinfunction "RXLED_22") (pintype "input"))
    )
    (net (code "104") (name "Net-(U1_CNSL-TXLED)") (class "Default")
      (node (ref "LED5") (pin "C") (pinfunction "C_C") (pintype "passive"))
      (node (ref "U1_CNSL") (pin "23") (pinfunction "TXLED_23") (pintype "input"))
    )
    (net (code "105") (name "Net-(U1_CNSL-USBDM)") (class "Default")
      (node (ref "U1_CNSL") (pin "16") (pinfunction "USBDM_16") (pintype "bidirectional"))
      (node (ref "X2_CNSL") (pin "D-") (pinfunction "D-_D-") (pintype "bidirectional"))
    )
    (net (code "106") (name "Net-(U1_CNSL-USBDP)") (class "Default")
      (node (ref "U1_CNSL") (pin "15") (pinfunction "USBDP_15") (pintype "bidirectional"))
      (node (ref "X2_CNSL") (pin "D+") (pinfunction "D+_D+") (pintype "bidirectional"))
    )
    (net (code "107") (name "Net-(U1_CNSL-VCC)") (class "Default")
      (node (ref "C10") (pin "1") (pinfunction "1_1") (pintype "passive"))
      (node (ref "F1_CNSL") (pin "2") (pinfunction "2_2") (pintype "bidirectional"))
      (node (ref "U1_CNSL") (pin "20") (pinfunction "VCC_20") (pintype "power_in"))
    )
    (net (code "108") (name "unconnected-(JP_PDI-Pad1)") (class "Default")
      (node (ref "JP_PDI") (pin "1") (pinfunction "1_1") (pintype "passive"))
    )
    (net (code "109") (name "unconnected-(JP_PDI-Pad5)") (class "Default")
      (node (ref "JP_PDI") (pin "5") (pinfunction "5_5") (pintype "passive"))
    )
    (net (code "110") (name "unconnected-(JP_PDI-Pad7)") (class "Default")
      (node (ref "JP_PDI") (pin "7") (pinfunction "7_7") (pintype "passive"))
    )
    (net (code "111") (name "unconnected-(JP_PDI-Pad8)") (class "Default")
      (node (ref "JP_PDI") (pin "8") (pinfunction "8_8") (pintype "passive"))
    )
    (net (code "112") (name "unconnected-(JP_PDI-Pad9)") (class "Default")
      (node (ref "JP_PDI") (pin "9") (pinfunction "9_9") (pintype "passive"))
    )
    (net (code "113") (name "unconnected-(U1_CNSL-CTS-Pad11)") (class "Default")
      (node (ref "U1_CNSL") (pin "11") (pinfunction "CTS_11") (pintype "input"))
    )
    (net (code "114") (name "unconnected-(U1_CNSL-DCD-Pad10)") (class "Default")
      (node (ref "U1_CNSL") (pin "10") (pinfunction "DCD_10") (pintype "input"))
    )
    (net (code "115") (name "unconnected-(U1_CNSL-DSR-Pad9)") (class "Default")
      (node (ref "U1_CNSL") (pin "9") (pinfunction "DSR_9") (pintype "input"))
    )
    (net (code "116") (name "unconnected-(U1_CNSL-DTR-Pad2)") (class "Default")
      (node (ref "U1_CNSL") (pin "2") (pinfunction "DTR_2") (pintype "output"))
    )
    (net (code "117") (name "unconnected-(U1_CNSL-OSCI-Pad27)") (class "Default")
      (node (ref "U1_CNSL") (pin "27") (pinfunction "OSCI_27") (pintype "input"))
    )
    (net (code "118") (name "unconnected-(U1_CNSL-OSCO-Pad28)") (class "Default")
      (node (ref "U1_CNSL") (pin "28") (pinfunction "OSCO_28") (pintype "output"))
    )
    (net (code "119") (name "unconnected-(U1_CNSL-PWREN-Pad14)") (class "Default")
      (node (ref "U1_CNSL") (pin "14") (pinfunction "PWREN_14") (pintype "input"))
    )
    (net (code "120") (name "unconnected-(U1_CNSL-RESET-Pad19)") (class "Default")
      (node (ref "U1_CNSL") (pin "19") (pinfunction "RESET_19") (pintype "input"))
    )
    (net (code "121") (name "unconnected-(U1_CNSL-RI-Pad6)") (class "Default")
      (node (ref "U1_CNSL") (pin "6") (pinfunction "RI_6") (pintype "input"))
    )
    (net (code "122") (name "unconnected-(U1_CNSL-RTS-Pad3)") (class "Default")
      (node (ref "U1_CNSL") (pin "3") (pinfunction "RTS_3") (pintype "output"))
    )
    (net (code "123") (name "unconnected-(U1_CNSL-SLEEP-Pad12)") (class "Default")
      (node (ref "U1_CNSL") (pin "12") (pinfunction "SLEEP_12") (pintype "input"))
    )
    (net (code "124") (name "unconnected-(U1_CNSL-TXDEN-Pad13)") (class "Default")
      (node (ref "U1_CNSL") (pin "13") (pinfunction "TXDEN_13") (pintype "input"))
    )
    (net (code "125") (name "unconnected-(U3-NC-Pad1)") (class "Default")
      (node (ref "U3") (pin "1") (pinfunction "NC_1") (pintype "bidirectional"))
    )
    (net (code "126") (name "unconnected-(U3-RSV-Pad8)") (class "Default")
      (node (ref "U3") (pin "8") (pinfunction "RSV_8") (pintype "bidirectional"))
    )
    (net (code "127") (name "unconnected-(U4_XMEGA-PQ2-Pad87)") (class "Default")
      (node (ref "U4_XMEGA") (pin "87") (pinfunction "PQ2_87") (pintype "bidirectional"))
    )
    (net (code "128") (name "unconnected-(U4_XMEGA-PQ3-Pad88)") (class "Default")
      (node (ref "U4_XMEGA") (pin "88") (pinfunction "PQ3_88") (pintype "bidirectional"))
    )
  )
)
